# G1_Bus_Breakout.net
KiCad netlist of a schematic drawn in Altium Designer
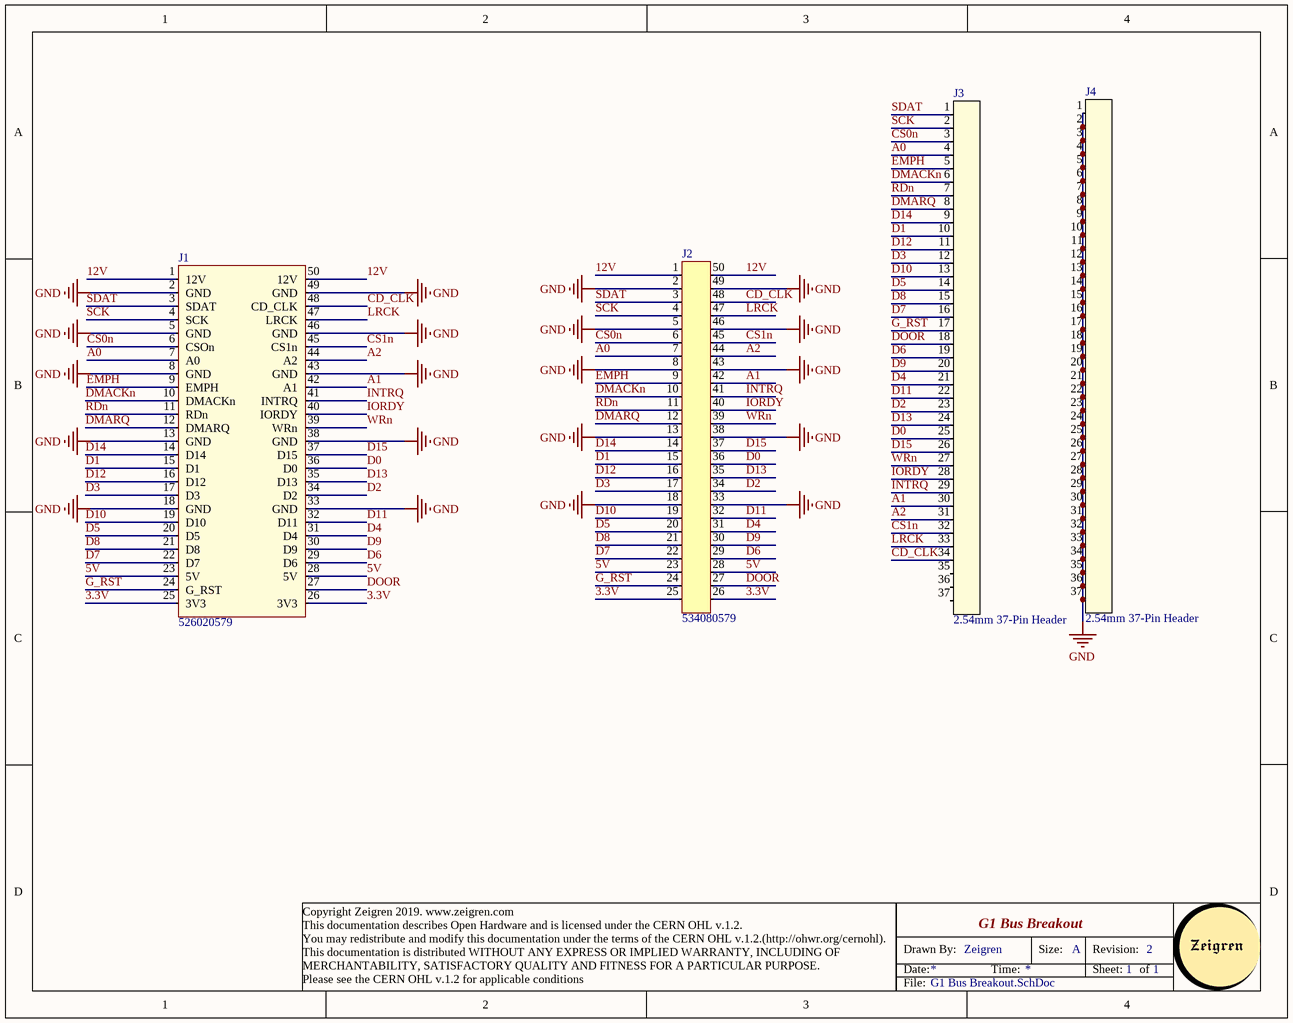
[diagram p0: G1 Bus Breakout.SchDoc]

(export (version "E")
  (design (tool "Eeschema 10.0.6"))
  (components
    (comp (ref "J1")
      (value "526020579")
      (footprint "GDROMCONN")
      (libsource (lib "MyLib") (part "GDROM CONN 52602-0579"))
    )
    (comp (ref "J2")
      (value "534080579")
      (footprint "GDROM Female CONN")
      (libsource (lib "MyLib") (part "GDROM Female Connector"))
    )
    (comp (ref "J3")
      (value "2.54mm 37-Pin Header")
      (footprint "37 Pins")
      (libsource (lib "MyLib") (part "2.54mm 37-Pin Header"))
    )
    (comp (ref "J4")
      (value "2.54mm 37-Pin Header")
      (footprint "37 Pins")
      (libsource (lib "MyLib") (part "2.54mm 37-Pin Header"))
    )
  )
  (nets
    (net (code "1") (name "/3.3V") (class "Default")
      (node (ref "J1") (pin "25") (pinfunction "3V3_25") (pintype "power_in"))
      (node (ref "J1") (pin "26") (pinfunction "3V3_26") (pintype "power_in"))
      (node (ref "J2") (pin "25") (pintype "input"))
      (node (ref "J2") (pin "26") (pintype "input"))
    )
    (net (code "2") (name "/5V") (class "Default")
      (node (ref "J1") (pin "23") (pinfunction "5V_23") (pintype "power_in"))
      (node (ref "J1") (pin "28") (pinfunction "5V_28") (pintype "power_in"))
      (node (ref "J2") (pin "23") (pintype "input"))
      (node (ref "J2") (pin "28") (pintype "input"))
    )
    (net (code "3") (name "/12V") (class "Default")
      (node (ref "J1") (pin "1") (pinfunction "12V_1") (pintype "power_in"))
      (node (ref "J1") (pin "50") (pinfunction "12V_50") (pintype "power_in"))
      (node (ref "J2") (pin "1") (pintype "input"))
      (node (ref "J2") (pin "50") (pintype "input"))
    )
    (net (code "4") (name "/A0") (class "Default")
      (node (ref "J1") (pin "7") (pinfunction "A0_7") (pintype "bidirectional"))
      (node (ref "J2") (pin "7") (pintype "input"))
      (node (ref "J3") (pin "4") (pintype "passive"))
    )
    (net (code "5") (name "/A1") (class "Default")
      (node (ref "J1") (pin "42") (pinfunction "A1_42") (pintype "bidirectional"))
      (node (ref "J2") (pin "42") (pintype "input"))
      (node (ref "J3") (pin "30") (pintype "passive"))
    )
    (net (code "6") (name "/A2") (class "Default")
      (node (ref "J1") (pin "44") (pinfunction "A2_44") (pintype "bidirectional"))
      (node (ref "J2") (pin "44") (pintype "input"))
      (node (ref "J3") (pin "31") (pintype "passive"))
    )
    (net (code "7") (name "/CD_CLK") (class "Default")
      (node (ref "J1") (pin "48") (pinfunction "CD_CLK_48") (pintype "bidirectional"))
      (node (ref "J2") (pin "48") (pintype "input"))
      (node (ref "J3") (pin "34") (pintype "passive"))
    )
    (net (code "8") (name "/CS0n") (class "Default")
      (node (ref "J1") (pin "6") (pinfunction "CSOn_6") (pintype "bidirectional"))
      (node (ref "J2") (pin "6") (pintype "input"))
      (node (ref "J3") (pin "3") (pintype "passive"))
    )
    (net (code "9") (name "/CS1n") (class "Default")
      (node (ref "J1") (pin "45") (pinfunction "CS1n_45") (pintype "bidirectional"))
      (node (ref "J2") (pin "45") (pintype "input"))
      (node (ref "J3") (pin "32") (pintype "passive"))
    )
    (net (code "10") (name "/D0") (class "Default")
      (node (ref "J1") (pin "36") (pinfunction "D0_36") (pintype "bidirectional"))
      (node (ref "J2") (pin "36") (pintype "input"))
      (node (ref "J3") (pin "25") (pintype "passive"))
    )
    (net (code "11") (name "/D1") (class "Default")
      (node (ref "J1") (pin "15") (pinfunction "D1_15") (pintype "bidirectional"))
      (node (ref "J2") (pin "15") (pintype "input"))
      (node (ref "J3") (pin "10") (pintype "passive"))
    )
    (net (code "12") (name "/D2") (class "Default")
      (node (ref "J1") (pin "34") (pinfunction "D2_34") (pintype "bidirectional"))
      (node (ref "J2") (pin "34") (pintype "input"))
      (node (ref "J3") (pin "23") (pintype "passive"))
    )
    (net (code "13") (name "/D3") (class "Default")
      (node (ref "J1") (pin "17") (pinfunction "D3_17") (pintype "bidirectional"))
      (node (ref "J2") (pin "17") (pintype "input"))
      (node (ref "J3") (pin "12") (pintype "passive"))
    )
    (net (code "14") (name "/D4") (class "Default")
      (node (ref "J1") (pin "31") (pinfunction "D4_31") (pintype "bidirectional"))
      (node (ref "J2") (pin "31") (pintype "input"))
      (node (ref "J3") (pin "21") (pintype "passive"))
    )
    (net (code "15") (name "/D5") (class "Default")
      (node (ref "J1") (pin "20") (pinfunction "D5_20") (pintype "bidirectional"))
      (node (ref "J2") (pin "20") (pintype "input"))
      (node (ref "J3") (pin "14") (pintype "passive"))
    )
    (net (code "16") (name "/D6") (class "Default")
      (node (ref "J1") (pin "29") (pinfunction "D6_29") (pintype "bidirectional"))
      (node (ref "J2") (pin "29") (pintype "input"))
      (node (ref "J3") (pin "19") (pintype "passive"))
    )
    (net (code "17") (name "/D7") (class "Default")
      (node (ref "J1") (pin "22") (pinfunction "D7_22") (pintype "bidirectional"))
      (node (ref "J2") (pin "22") (pintype "input"))
      (node (ref "J3") (pin "16") (pintype "passive"))
    )
    (net (code "18") (name "/D8") (class "Default")
      (node (ref "J1") (pin "21") (pinfunction "D8_21") (pintype "bidirectional"))
      (node (ref "J2") (pin "21") (pintype "input"))
      (node (ref "J3") (pin "15") (pintype "passive"))
    )
    (net (code "19") (name "/D9") (class "Default")
      (node (ref "J1") (pin "30") (pinfunction "D9_30") (pintype "bidirectional"))
      (node (ref "J2") (pin "30") (pintype "input"))
      (node (ref "J3") (pin "20") (pintype "passive"))
    )
    (net (code "20") (name "/D10") (class "Default")
      (node (ref "J1") (pin "19") (pinfunction "D10_19") (pintype "bidirectional"))
      (node (ref "J2") (pin "19") (pintype "input"))
      (node (ref "J3") (pin "13") (pintype "passive"))
    )
    (net (code "21") (name "/D11") (class "Default")
      (node (ref "J1") (pin "32") (pinfunction "D11_32") (pintype "bidirectional"))
      (node (ref "J2") (pin "32") (pintype "input"))
      (node (ref "J3") (pin "22") (pintype "passive"))
    )
    (net (code "22") (name "/D12") (class "Default")
      (node (ref "J1") (pin "16") (pinfunction "D12_16") (pintype "bidirectional"))
      (node (ref "J2") (pin "16") (pintype "input"))
      (node (ref "J3") (pin "11") (pintype "passive"))
    )
    (net (code "23") (name "/D13") (class "Default")
      (node (ref "J1") (pin "35") (pinfunction "D13_35") (pintype "bidirectional"))
      (node (ref "J2") (pin "35") (pintype "input"))
      (node (ref "J3") (pin "24") (pintype "passive"))
    )
    (net (code "24") (name "/D14") (class "Default")
      (node (ref "J1") (pin "14") (pinfunction "D14_14") (pintype "bidirectional"))
      (node (ref "J2") (pin "14") (pintype "input"))
      (node (ref "J3") (pin "9") (pintype "passive"))
    )
    (net (code "25") (name "/D15") (class "Default")
      (node (ref "J1") (pin "37") (pinfunction "D15_37") (pintype "bidirectional"))
      (node (ref "J2") (pin "37") (pintype "input"))
      (node (ref "J3") (pin "26") (pintype "passive"))
    )
    (net (code "26") (name "/DMACKn") (class "Default")
      (node (ref "J1") (pin "10") (pinfunction "DMACKn_10") (pintype "bidirectional"))
      (node (ref "J2") (pin "10") (pintype "input"))
      (node (ref "J3") (pin "6") (pintype "passive"))
    )
    (net (code "27") (name "/DMARQ") (class "Default")
      (node (ref "J1") (pin "12") (pinfunction "DMARQ_12") (pintype "bidirectional"))
      (node (ref "J2") (pin "12") (pintype "input"))
      (node (ref "J3") (pin "8") (pintype "passive"))
    )
    (net (code "28") (name "/DOOR") (class "Default")
      (node (ref "J1") (pin "27") (pintype "bidirectional"))
      (node (ref "J2") (pin "27") (pintype "input"))
      (node (ref "J3") (pin "18") (pintype "passive"))
    )
    (net (code "29") (name "/EMPH") (class "Default")
      (node (ref "J1") (pin "9") (pinfunction "EMPH_9") (pintype "bidirectional"))
      (node (ref "J2") (pin "9") (pintype "input"))
      (node (ref "J3") (pin "5") (pintype "passive"))
    )
    (net (code "30") (name "/G_RST") (class "Default")
      (node (ref "J1") (pin "24") (pinfunction "G_RST_24") (pintype "bidirectional"))
      (node (ref "J2") (pin "24") (pintype "input"))
      (node (ref "J3") (pin "17") (pintype "passive"))
    )
    (net (code "31") (name "/INTRQ") (class "Default")
      (node (ref "J1") (pin "41") (pinfunction "INTRQ_41") (pintype "bidirectional"))
      (node (ref "J2") (pin "41") (pintype "input"))
      (node (ref "J3") (pin "29") (pintype "passive"))
    )
    (net (code "32") (name "/IORDY") (class "Default")
      (node (ref "J1") (pin "40") (pinfunction "IORDY_40") (pintype "bidirectional"))
      (node (ref "J2") (pin "40") (pintype "input"))
      (node (ref "J3") (pin "28") (pintype "passive"))
    )
    (net (code "33") (name "/LRCK") (class "Default")
      (node (ref "J1") (pin "47") (pinfunction "LRCK_47") (pintype "bidirectional"))
      (node (ref "J2") (pin "47") (pintype "input"))
      (node (ref "J3") (pin "33") (pintype "passive"))
    )
    (net (code "34") (name "/RDn") (class "Default")
      (node (ref "J1") (pin "11") (pinfunction "RDn_11") (pintype "bidirectional"))
      (node (ref "J2") (pin "11") (pintype "input"))
      (node (ref "J3") (pin "7") (pintype "passive"))
    )
    (net (code "35") (name "/SCK") (class "Default")
      (node (ref "J1") (pin "4") (pinfunction "SCK_4") (pintype "bidirectional"))
      (node (ref "J2") (pin "4") (pintype "input"))
      (node (ref "J3") (pin "2") (pintype "passive"))
    )
    (net (code "36") (name "/SDAT") (class "Default")
      (node (ref "J1") (pin "3") (pinfunction "SDAT_3") (pintype "bidirectional"))
      (node (ref "J2") (pin "3") (pintype "input"))
      (node (ref "J3") (pin "1") (pintype "passive"))
    )
    (net (code "37") (name "/WRn") (class "Default")
      (node (ref "J1") (pin "39") (pinfunction "WRn_39") (pintype "bidirectional"))
      (node (ref "J2") (pin "39") (pintype "input"))
      (node (ref "J3") (pin "27") (pintype "passive"))
    )
    (net (code "38") (name "GND") (class "Default")
      (node (ref "J1") (pin "13") (pinfunction "GND_13") (pintype "power_in"))
      (node (ref "J1") (pin "18") (pinfunction "GND_18") (pintype "power_in"))
      (node (ref "J1") (pin "2") (pinfunction "GND_2") (pintype "power_in"))
      (node (ref "J1") (pin "33") (pinfunction "GND_33") (pintype "power_in"))
      (node (ref "J1") (pin "38") (pinfunction "GND_38") (pintype "power_in"))
      (node (ref "J1") (pin "43") (pinfunction "GND_43") (pintype "power_in"))
      (node (ref "J1") (pin "46") (pinfunction "GND_46") (pintype "power_in"))
      (node (ref "J1") (pin "49") (pinfunction "GND_49") (pintype "power_in"))
      (node (ref "J1") (pin "5") (pinfunction "GND_5") (pintype "power_in"))
      (node (ref "J1") (pin "8") (pinfunction "GND_8") (pintype "power_in"))
      (node (ref "J2") (pin "13") (pintype "input"))
      (node (ref "J2") (pin "18") (pintype "input"))
      (node (ref "J2") (pin "2") (pintype "input"))
      (node (ref "J2") (pin "33") (pintype "input"))
      (node (ref "J2") (pin "38") (pintype "input"))
      (node (ref "J2") (pin "43") (pintype "input"))
      (node (ref "J2") (pin "46") (pintype "input"))
      (node (ref "J2") (pin "49") (pintype "input"))
      (node (ref "J2") (pin "5") (pintype "input"))
      (node (ref "J2") (pin "8") (pintype "input"))
      (node (ref "J4") (pin "1") (pintype "passive"))
      (node (ref "J4") (pin "10") (pintype "passive"))
      (node (ref "J4") (pin "11") (pintype "passive"))
      (node (ref "J4") (pin "12") (pintype "passive"))
      (node (ref "J4") (pin "13") (pintype "passive"))
      (node (ref "J4") (pin "14") (pintype "passive"))
      (node (ref "J4") (pin "15") (pintype "passive"))
      (node (ref "J4") (pin "16") (pintype "passive"))
      (node (ref "J4") (pin "17") (pintype "passive"))
      (node (ref "J4") (pin "18") (pintype "passive"))
      (node (ref "J4") (pin "19") (pintype "passive"))
      (node (ref "J4") (pin "2") (pintype "passive"))
      (node (ref "J4") (pin "20") (pintype "passive"))
      (node (ref "J4") (pin "21") (pintype "passive"))
      (node (ref "J4") (pin "22") (pintype "passive"))
      (node (ref "J4") (pin "23") (pintype "passive"))
      (node (ref "J4") (pin "24") (pintype "passive"))
      (node (ref "J4") (pin "25") (pintype "passive"))
      (node (ref "J4") (pin "26") (pintype "passive"))
      (node (ref "J4") (pin "27") (pintype "passive"))
      (node (ref "J4") (pin "28") (pintype "passive"))
      (node (ref "J4") (pin "29") (pintype "passive"))
      (node (ref "J4") (pin "3") (pintype "passive"))
      (node (ref "J4") (pin "30") (pintype "passive"))
      (node (ref "J4") (pin "31") (pintype "passive"))
      (node (ref "J4") (pin "32") (pintype "passive"))
      (node (ref "J4") (pin "33") (pintype "passive"))
      (node (ref "J4") (pin "34") (pintype "passive"))
      (node (ref "J4") (pin "35") (pintype "passive"))
      (node (ref "J4") (pin "36") (pintype "passive"))
      (node (ref "J4") (pin "37") (pintype "passive"))
      (node (ref "J4") (pin "4") (pintype "passive"))
      (node (ref "J4") (pin "5") (pintype "passive"))
      (node (ref "J4") (pin "6") (pintype "passive"))
      (node (ref "J4") (pin "7") (pintype "passive"))
      (node (ref "J4") (pin "8") (pintype "passive"))
      (node (ref "J4") (pin "9") (pintype "passive"))
    )
    (net (code "39") (name "unconnected-(J3-Pad35)") (class "Default")
      (node (ref "J3") (pin "35") (pintype "passive"))
    )
    (net (code "40") (name "unconnected-(J3-Pad36)") (class "Default")
      (node (ref "J3") (pin "36") (pintype "passive"))
    )
    (net (code "41") (name "unconnected-(J3-Pad37)") (class "Default")
      (node (ref "J3") (pin "37") (pintype "passive"))
    )
  )
)
